# design.net
KiCad netlist of a schematic drawn in Altium Designer
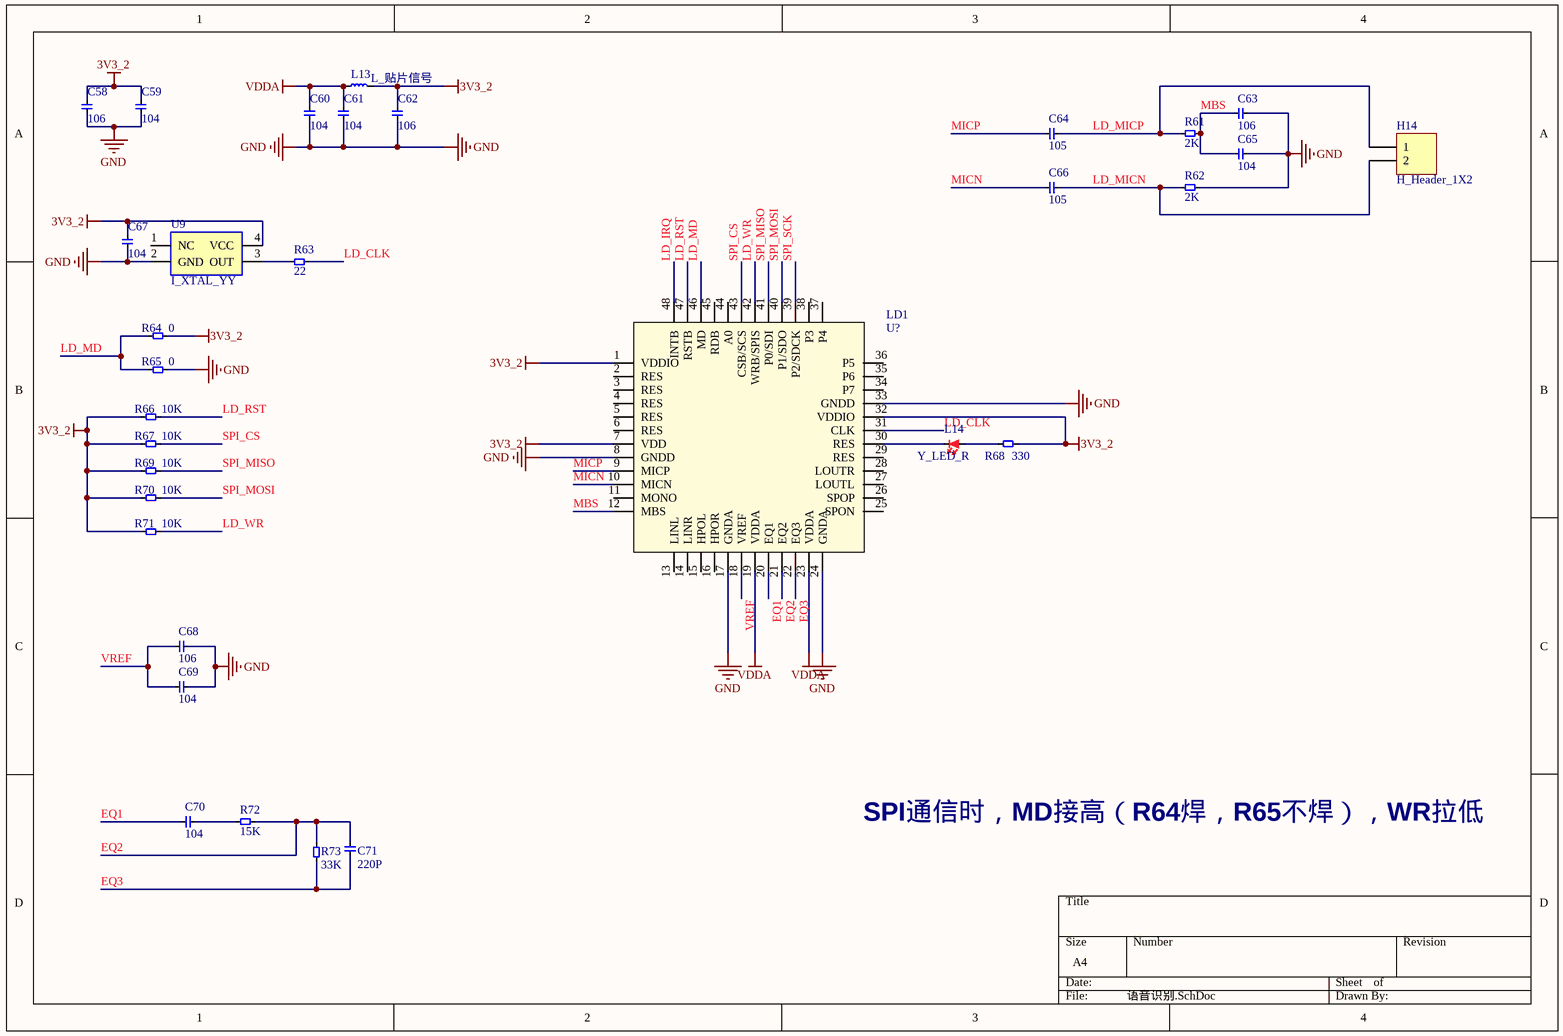
[diagram p0: 语音识别.SchDoc]

(export (version "E")
  (design (tool "Eeschema 10.0.6"))
  (components
    (comp (ref "C58")
      (value "106")
      (footprint "C_0603")
      (description "无极性贴片电容")
      (libsource (lib "电阻电容电感库") (part "C_无极贴片"))
    )
    (comp (ref "C59")
      (value "104")
      (footprint "C_0603")
      (description "无极性贴片电容")
      (libsource (lib "电阻电容电感库") (part "C_无极贴片"))
    )
    (comp (ref "C60")
      (value "104")
      (footprint "C_0603")
      (description "无极性贴片电容")
      (libsource (lib "电阻电容电感库") (part "C_无极贴片"))
    )
    (comp (ref "C61")
      (value "104")
      (footprint "C_0603")
      (description "无极性贴片电容")
      (libsource (lib "电阻电容电感库") (part "C_无极贴片"))
    )
    (comp (ref "C62")
      (value "106")
      (footprint "C_0603")
      (description "无极性贴片电容")
      (libsource (lib "电阻电容电感库") (part "C_无极贴片"))
    )
    (comp (ref "C63")
      (value "106")
      (footprint "C_0603")
      (description "无极性贴片电容")
      (libsource (lib "电阻电容电感库") (part "C_无极贴片"))
    )
    (comp (ref "C64")
      (value "105")
      (footprint "C_0603")
      (description "无极性贴片电容")
      (libsource (lib "电阻电容电感库") (part "C_无极贴片"))
    )
    (comp (ref "C65")
      (value "104")
      (footprint "C_0603")
      (description "无极性贴片电容")
      (libsource (lib "电阻电容电感库") (part "C_无极贴片"))
    )
    (comp (ref "C66")
      (value "105")
      (footprint "C_0603")
      (description "无极性贴片电容")
      (libsource (lib "电阻电容电感库") (part "C_无极贴片"))
    )
    (comp (ref "C67")
      (value "104")
      (footprint "C_0603")
      (description "无极性贴片电容")
      (libsource (lib "电阻电容电感库") (part "C_无极贴片"))
    )
    (comp (ref "C68")
      (value "106")
      (footprint "C_0603")
      (description "无极性贴片电容")
      (libsource (lib "电阻电容电感库") (part "C_无极贴片"))
    )
    (comp (ref "C69")
      (value "104")
      (footprint "C_0603")
      (description "无极性贴片电容")
      (libsource (lib "电阻电容电感库") (part "C_无极贴片"))
    )
    (comp (ref "C70")
      (value "104")
      (footprint "C_0603")
      (description "无极性贴片电容")
      (libsource (lib "电阻电容电感库") (part "C_无极贴片"))
    )
    (comp (ref "C71")
      (value "220P")
      (footprint "C_0603")
      (description "无极性贴片电容")
      (libsource (lib "电阻电容电感库") (part "C_无极贴片"))
    )
    (comp (ref "H14")
      (value "H_Header_1X2")
      (footprint "H_Header_1X2")
      (description "单排2针排针")
      (fields (field (name "PUBLISHER") "Altium Limited"))
      (libsource (lib "接插件") (part "H_Header_1X2"))
    )
    (comp (ref "L13")
      (value "L_贴片信号")
      (footprint "L_0805")
      (description "贴片信号电感")
      (libsource (lib "电阻电容电感库") (part "L_贴片信号"))
    )
    (comp (ref "L14")
      (value "Y_LED_R")
      (footprint "Y_LED_0805_R")
      (description "红色LED")
      (libsource (lib "声光元件") (part "Y_LED_R"))
    )
    (comp (ref "LD1") (value "U?") (footprint "QFN48") (libsource (lib "王建勇") (part "LD3320")))
    (comp (ref "R61")
      (value "2K")
      (footprint "R_0603")
      (description "贴片电阻")
      (libsource (lib "电阻电容电感库") (part "R_贴片"))
    )
    (comp (ref "R62")
      (value "2K")
      (footprint "R_0603")
      (description "贴片电阻")
      (libsource (lib "电阻电容电感库") (part "R_贴片"))
    )
    (comp (ref "R63")
      (value "22")
      (footprint "R_0603")
      (description "贴片电阻")
      (libsource (lib "电阻电容电感库") (part "R_贴片"))
    )
    (comp (ref "R64")
      (value "0")
      (footprint "R_0603")
      (description "贴片电阻")
      (libsource (lib "电阻电容电感库") (part "R_贴片"))
    )
    (comp (ref "R65")
      (value "0")
      (footprint "R_0603")
      (description "贴片电阻")
      (libsource (lib "电阻电容电感库") (part "R_贴片"))
    )
    (comp (ref "R66")
      (value "10K")
      (footprint "R_0603")
      (description "贴片电阻")
      (libsource (lib "电阻电容电感库") (part "R_贴片"))
    )
    (comp (ref "R67")
      (value "10K")
      (footprint "R_0603")
      (description "贴片电阻")
      (libsource (lib "电阻电容电感库") (part "R_贴片"))
    )
    (comp (ref "R68")
      (value "330")
      (footprint "R_0603")
      (description "贴片电阻")
      (libsource (lib "电阻电容电感库") (part "R_贴片"))
    )
    (comp (ref "R69")
      (value "10K")
      (footprint "R_0603")
      (description "贴片电阻")
      (libsource (lib "电阻电容电感库") (part "R_贴片"))
    )
    (comp (ref "R70")
      (value "10K")
      (footprint "R_0603")
      (description "贴片电阻")
      (libsource (lib "电阻电容电感库") (part "R_贴片"))
    )
    (comp (ref "R71")
      (value "10K")
      (footprint "R_0603")
      (description "贴片电阻")
      (libsource (lib "电阻电容电感库") (part "R_贴片"))
    )
    (comp (ref "R72")
      (value "15K")
      (footprint "R_0603")
      (description "贴片电阻")
      (libsource (lib "电阻电容电感库") (part "R_贴片"))
    )
    (comp (ref "R73")
      (value "33K")
      (footprint "R_0603")
      (description "贴片电阻")
      (libsource (lib "电阻电容电感库") (part "R_贴片"))
    )
    (comp (ref "U9")
      (value "I_XTAL_YY")
      (footprint "I_XTAL_YYSMD_3.2X2.5")
      (description "有源晶振")
      (libsource (lib "集成器件") (part "I_XTAL_YY"))
    )
  )
  (nets
    (net (code "1") (name "/EQ1") (class "Default")
      (node (ref "C70") (pin "2") (pinfunction "2_2") (pintype "passive"))
      (node (ref "LD1") (pin "20") (pinfunction "EQ1_20") (pintype "passive"))
    )
    (net (code "2") (name "/EQ2") (class "Default")
      (node (ref "C71") (pin "1") (pinfunction "1_1") (pintype "passive"))
      (node (ref "LD1") (pin "21") (pinfunction "EQ2_21") (pintype "passive"))
      (node (ref "R72") (pin "2") (pintype "passive"))
      (node (ref "R73") (pin "2") (pintype "passive"))
    )
    (net (code "3") (name "/EQ3") (class "Default")
      (node (ref "C71") (pin "2") (pinfunction "2_2") (pintype "passive"))
      (node (ref "LD1") (pin "22") (pinfunction "EQ3_22") (pintype "passive"))
      (node (ref "R73") (pin "1") (pintype "passive"))
    )
    (net (code "4") (name "/LD_CLK") (class "Default")
      (node (ref "LD1") (pin "31") (pinfunction "CLK_31") (pintype "passive"))
      (node (ref "R63") (pin "2") (pintype "passive"))
    )
    (net (code "5") (name "/LD_IRQ") (class "Default")
      (node (ref "LD1") (pin "48") (pinfunction "INTB_48") (pintype "passive"))
    )
    (net (code "6") (name "/LD_MD") (class "Default")
      (node (ref "LD1") (pin "46") (pinfunction "MD_46") (pintype "passive"))
      (node (ref "R64") (pin "1") (pintype "passive"))
      (node (ref "R65") (pin "1") (pintype "passive"))
    )
    (net (code "7") (name "/LD_MICN") (class "Default")
      (node (ref "C66") (pin "2") (pinfunction "2_2") (pintype "passive"))
      (node (ref "H14") (pin "2") (pinfunction "2_2") (pintype "passive"))
      (node (ref "R62") (pin "1") (pintype "passive"))
    )
    (net (code "8") (name "/LD_MICP") (class "Default")
      (node (ref "C64") (pin "2") (pinfunction "2_2") (pintype "passive"))
      (node (ref "H14") (pin "1") (pinfunction "1_1") (pintype "passive"))
      (node (ref "R61") (pin "1") (pintype "passive"))
    )
    (net (code "9") (name "/LD_RST") (class "Default")
      (node (ref "LD1") (pin "47") (pinfunction "RSTB_47") (pintype "passive"))
      (node (ref "R66") (pin "2") (pintype "passive"))
    )
    (net (code "10") (name "/LD_WR") (class "Default")
      (node (ref "LD1") (pin "42") (pinfunction "WRB/SPIS_42") (pintype "passive"))
      (node (ref "R71") (pin "2") (pintype "passive"))
    )
    (net (code "11") (name "/MBS") (class "Default")
      (node (ref "C63") (pin "1") (pinfunction "1_1") (pintype "passive"))
      (node (ref "C65") (pin "1") (pinfunction "1_1") (pintype "passive"))
      (node (ref "LD1") (pin "12") (pinfunction "MBS_12") (pintype "passive"))
      (node (ref "R61") (pin "2") (pintype "passive"))
    )
    (net (code "12") (name "/MICN") (class "Default")
      (node (ref "C66") (pin "1") (pinfunction "1_1") (pintype "passive"))
      (node (ref "LD1") (pin "10") (pinfunction "MICN_10") (pintype "passive"))
    )
    (net (code "13") (name "/MICP") (class "Default")
      (node (ref "C64") (pin "1") (pinfunction "1_1") (pintype "passive"))
      (node (ref "LD1") (pin "9") (pinfunction "MICP_9") (pintype "passive"))
    )
    (net (code "14") (name "/SPI_CS") (class "Default")
      (node (ref "LD1") (pin "43") (pinfunction "CSB/SCS_43") (pintype "passive"))
      (node (ref "R67") (pin "2") (pintype "passive"))
    )
    (net (code "15") (name "/SPI_MISO") (class "Default")
      (node (ref "LD1") (pin "41") (pinfunction "P0/SDI_41") (pintype "passive"))
      (node (ref "R69") (pin "2") (pintype "passive"))
    )
    (net (code "16") (name "/SPI_MOSI") (class "Default")
      (node (ref "LD1") (pin "40") (pinfunction "P1/SDO_40") (pintype "passive"))
      (node (ref "R70") (pin "2") (pintype "passive"))
    )
    (net (code "17") (name "/SPI_SCK") (class "Default")
      (node (ref "LD1") (pin "39") (pinfunction "P2/SDCK_39") (pintype "passive"))
    )
    (net (code "18") (name "/VREF") (class "Default")
      (node (ref "C68") (pin "2") (pinfunction "2_2") (pintype "passive"))
      (node (ref "C69") (pin "2") (pinfunction "2_2") (pintype "passive"))
      (node (ref "LD1") (pin "18") (pinfunction "VREF_18") (pintype "passive"))
    )
    (net (code "19") (name "3V3_2") (class "Default")
      (node (ref "C58") (pin "2") (pinfunction "2_2") (pintype "passive"))
      (node (ref "C59") (pin "2") (pinfunction "2_2") (pintype "passive"))
      (node (ref "C62") (pin "2") (pinfunction "2_2") (pintype "passive"))
      (node (ref "C67") (pin "2") (pinfunction "2_2") (pintype "passive"))
      (node (ref "L13") (pin "2") (pinfunction "2_2") (pintype "passive"))
      (node (ref "LD1") (pin "1") (pinfunction "VDDIO_1") (pintype "passive"))
      (node (ref "LD1") (pin "32") (pinfunction "VDDIO_32") (pintype "passive"))
      (node (ref "LD1") (pin "7") (pinfunction "VDD_7") (pintype "passive"))
      (node (ref "R64") (pin "2") (pintype "passive"))
      (node (ref "R66") (pin "1") (pintype "passive"))
      (node (ref "R67") (pin "1") (pintype "passive"))
      (node (ref "R68") (pin "2") (pintype "passive"))
      (node (ref "R69") (pin "1") (pintype "passive"))
      (node (ref "R70") (pin "1") (pintype "passive"))
      (node (ref "R71") (pin "1") (pintype "passive"))
      (node (ref "U9") (pin "4") (pinfunction "VCC_4") (pintype "passive"))
    )
    (net (code "20") (name "GND") (class "Default")
      (node (ref "C58") (pin "1") (pinfunction "1_1") (pintype "passive"))
      (node (ref "C59") (pin "1") (pinfunction "1_1") (pintype "passive"))
      (node (ref "C60") (pin "1") (pinfunction "1_1") (pintype "passive"))
      (node (ref "C61") (pin "1") (pinfunction "1_1") (pintype "passive"))
      (node (ref "C62") (pin "1") (pinfunction "1_1") (pintype "passive"))
      (node (ref "C63") (pin "2") (pinfunction "2_2") (pintype "passive"))
      (node (ref "C65") (pin "2") (pinfunction "2_2") (pintype "passive"))
      (node (ref "C67") (pin "1") (pinfunction "1_1") (pintype "passive"))
      (node (ref "C68") (pin "1") (pinfunction "1_1") (pintype "passive"))
      (node (ref "C69") (pin "1") (pinfunction "1_1") (pintype "passive"))
      (node (ref "LD1") (pin "17") (pinfunction "GNDA_17") (pintype "passive"))
      (node (ref "LD1") (pin "24") (pinfunction "GNDA_24") (pintype "passive"))
      (node (ref "LD1") (pin "33") (pinfunction "GNDD_33") (pintype "passive"))
      (node (ref "LD1") (pin "8") (pinfunction "GNDD_8") (pintype "passive"))
      (node (ref "R62") (pin "2") (pintype "passive"))
      (node (ref "R65") (pin "2") (pintype "passive"))
      (node (ref "U9") (pin "2") (pinfunction "GND_2") (pintype "passive"))
    )
    (net (code "21") (name "Net-(C70-Pad1)") (class "Default")
      (node (ref "C70") (pin "1") (pinfunction "1_1") (pintype "passive"))
      (node (ref "R72") (pin "1") (pintype "passive"))
    )
    (net (code "22") (name "Net-(L14-Pad1)") (class "Default")
      (node (ref "L14") (pin "1") (pintype "passive"))
      (node (ref "R68") (pin "1") (pintype "passive"))
    )
    (net (code "23") (name "Net-(L14-Pad2)") (class "Default")
      (node (ref "L14") (pin "2") (pintype "passive"))
      (node (ref "LD1") (pin "30") (pinfunction "RES_30") (pintype "passive"))
    )
    (net (code "24") (name "Net-(U9-OUT)") (class "Default")
      (node (ref "R63") (pin "1") (pintype "passive"))
      (node (ref "U9") (pin "3") (pinfunction "OUT_3") (pintype "passive"))
    )
    (net (code "25") (name "VDDA") (class "Default")
      (node (ref "C60") (pin "2") (pinfunction "2_2") (pintype "passive"))
      (node (ref "C61") (pin "2") (pinfunction "2_2") (pintype "passive"))
      (node (ref "L13") (pin "1") (pinfunction "1_1") (pintype "passive"))
      (node (ref "LD1") (pin "19") (pinfunction "VDDA_19") (pintype "passive"))
      (node (ref "LD1") (pin "23") (pinfunction "VDDA_23") (pintype "passive"))
    )
    (net (code "26") (name "unconnected-(LD1-A0-Pad44)") (class "Default")
      (node (ref "LD1") (pin "44") (pinfunction "A0_44") (pintype "passive"))
    )
    (net (code "27") (name "unconnected-(LD1-HPOL-Pad15)") (class "Default")
      (node (ref "LD1") (pin "15") (pinfunction "HPOL_15") (pintype "passive"))
    )
    (net (code "28") (name "unconnected-(LD1-HPOR-Pad16)") (class "Default")
      (node (ref "LD1") (pin "16") (pinfunction "HPOR_16") (pintype "passive"))
    )
    (net (code "29") (name "unconnected-(LD1-LINL-Pad13)") (class "Default")
      (node (ref "LD1") (pin "13") (pinfunction "LINL_13") (pintype "passive"))
    )
    (net (code "30") (name "unconnected-(LD1-LINR-Pad14)") (class "Default")
      (node (ref "LD1") (pin "14") (pinfunction "LINR_14") (pintype "passive"))
    )
    (net (code "31") (name "unconnected-(LD1-LOUTL-Pad27)") (class "Default")
      (node (ref "LD1") (pin "27") (pinfunction "LOUTL_27") (pintype "passive"))
    )
    (net (code "32") (name "unconnected-(LD1-LOUTR-Pad28)") (class "Default")
      (node (ref "LD1") (pin "28") (pinfunction "LOUTR_28") (pintype "passive"))
    )
    (net (code "33") (name "unconnected-(LD1-MONO-Pad11)") (class "Default")
      (node (ref "LD1") (pin "11") (pinfunction "MONO_11") (pintype "passive"))
    )
    (net (code "34") (name "unconnected-(LD1-P3-Pad38)") (class "Default")
      (node (ref "LD1") (pin "38") (pinfunction "P3_38") (pintype "passive"))
    )
    (net (code "35") (name "unconnected-(LD1-P4-Pad37)") (class "Default")
      (node (ref "LD1") (pin "37") (pinfunction "P4_37") (pintype "passive"))
    )
    (net (code "36") (name "unconnected-(LD1-P5-Pad36)") (class "Default")
      (node (ref "LD1") (pin "36") (pinfunction "P5_36") (pintype "passive"))
    )
    (net (code "37") (name "unconnected-(LD1-P6-Pad35)") (class "Default")
      (node (ref "LD1") (pin "35") (pinfunction "P6_35") (pintype "passive"))
    )
    (net (code "38") (name "unconnected-(LD1-P7-Pad34)") (class "Default")
      (node (ref "LD1") (pin "34") (pinfunction "P7_34") (pintype "passive"))
    )
    (net (code "39") (name "unconnected-(LD1-RDB-Pad45)") (class "Default")
      (node (ref "LD1") (pin "45") (pinfunction "RDB_45") (pintype "passive"))
    )
    (net (code "40") (name "unconnected-(LD1-RES-Pad2)") (class "Default")
      (node (ref "LD1") (pin "2") (pinfunction "RES_2") (pintype "passive"))
    )
    (net (code "41") (name "unconnected-(LD1-RES-Pad3)") (class "Default")
      (node (ref "LD1") (pin "3") (pinfunction "RES_3") (pintype "passive"))
    )
    (net (code "42") (name "unconnected-(LD1-RES-Pad4)") (class "Default")
      (node (ref "LD1") (pin "4") (pinfunction "RES_4") (pintype "passive"))
    )
    (net (code "43") (name "unconnected-(LD1-RES-Pad5)") (class "Default")
      (node (ref "LD1") (pin "5") (pinfunction "RES_5") (pintype "passive"))
    )
    (net (code "44") (name "unconnected-(LD1-RES-Pad6)") (class "Default")
      (node (ref "LD1") (pin "6") (pinfunction "RES_6") (pintype "passive"))
    )
    (net (code "45") (name "unconnected-(LD1-RES-Pad29)") (class "Default")
      (node (ref "LD1") (pin "29") (pinfunction "RES_29") (pintype "passive"))
    )
    (net (code "46") (name "unconnected-(LD1-SPON-Pad25)") (class "Default")
      (node (ref "LD1") (pin "25") (pinfunction "SPON_25") (pintype "passive"))
    )
    (net (code "47") (name "unconnected-(LD1-SPOP-Pad26)") (class "Default")
      (node (ref "LD1") (pin "26") (pinfunction "SPOP_26") (pintype "passive"))
    )
    (net (code "48") (name "unconnected-(U9-NC-Pad1)") (class "Default")
      (node (ref "U9") (pin "1") (pinfunction "NC_1") (pintype "passive"))
    )
  )
)
